# monitoring_1.net
KiCad netlist of a schematic drawn in EAGLE
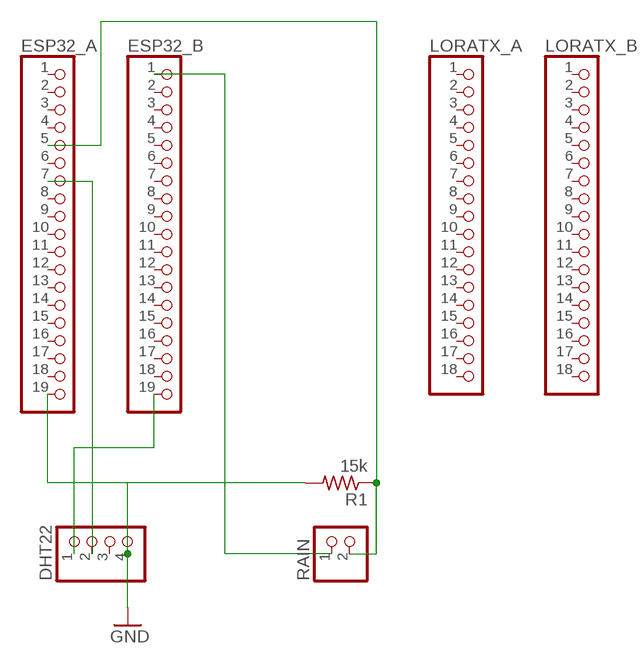
[diagram p0: schematic, sheet 1]

(export (version "E")
  (design (tool "Eeschema 10.0.6"))
  (components
    (comp (ref "DHT22")
      (value "PINHD-1X4")
      (footprint "eagle-import:1X04")
      (libsource (lib "eagle-import") (part "PINHD-1X4"))
    )
    (comp (ref "ESP32_A")
      (value "PINHD-1X19")
      (footprint "eagle-import:1X19")
      (libsource (lib "eagle-import") (part "PINHD-1X19"))
    )
    (comp (ref "ESP32_B")
      (value "PINHD-1X19")
      (footprint "eagle-import:1X19")
      (libsource (lib "eagle-import") (part "PINHD-1X19"))
    )
    (comp (ref "LORATX_A")
      (value "PINHD-1X18")
      (footprint "eagle-import:1X18")
      (libsource (lib "eagle-import") (part "PINHD-1X18"))
    )
    (comp (ref "LORATX_B")
      (value "PINHD-1X18")
      (footprint "eagle-import:1X18")
      (libsource (lib "eagle-import") (part "PINHD-1X18"))
    )
    (comp (ref "R1")
      (value "15k")
      (footprint "eagle-import:0204_7")
      (libsource (lib "eagle-import") (part "R-US_0204/7"))
    )
    (comp (ref "RAIN")
      (value "PINHD-1X2")
      (footprint "eagle-import:1X02")
      (libsource (lib "eagle-import") (part "PINHD-1X2"))
    )
  )
  (nets
    (net (code "1") (name "GND") (class "Default")
      (node (ref "DHT22") (pin "4") (pinfunction "4_4") (pintype "passive"))
      (node (ref "ESP32_A") (pin "19") (pinfunction "19_19") (pintype "passive"))
      (node (ref "R1") (pin "2") (pinfunction "2_2") (pintype "passive"))
    )
    (net (code "2") (name "Net-(DHT22-Pad1)") (class "Default")
      (node (ref "DHT22") (pin "1") (pinfunction "1_1") (pintype "passive"))
      (node (ref "ESP32_B") (pin "19") (pinfunction "19_19") (pintype "passive"))
    )
    (net (code "3") (name "Net-(DHT22-Pad2)") (class "Default")
      (node (ref "DHT22") (pin "2") (pinfunction "2_2") (pintype "passive"))
      (node (ref "ESP32_A") (pin "7") (pinfunction "7_7") (pintype "passive"))
    )
    (net (code "4") (name "Net-(ESP32_A-Pad5)") (class "Default")
      (node (ref "ESP32_A") (pin "5") (pinfunction "5_5") (pintype "passive"))
      (node (ref "R1") (pin "1") (pinfunction "1_1") (pintype "passive"))
      (node (ref "RAIN") (pin "2") (pinfunction "2_2") (pintype "passive"))
    )
    (net (code "5") (name "Net-(ESP32_B-Pad1)") (class "Default")
      (node (ref "ESP32_B") (pin "1") (pinfunction "1_1") (pintype "passive"))
      (node (ref "RAIN") (pin "1") (pinfunction "1_1") (pintype "passive"))
    )
    (net (code "6") (name "unconnected-(DHT22-Pad3)") (class "Default")
      (node (ref "DHT22") (pin "3") (pinfunction "3_3") (pintype "passive"))
    )
    (net (code "7") (name "unconnected-(ESP32_A-Pad1)") (class "Default")
      (node (ref "ESP32_A") (pin "1") (pinfunction "1_1") (pintype "passive"))
    )
    (net (code "8") (name "unconnected-(ESP32_A-Pad2)") (class "Default")
      (node (ref "ESP32_A") (pin "2") (pinfunction "2_2") (pintype "passive"))
    )
    (net (code "9") (name "unconnected-(ESP32_A-Pad3)") (class "Default")
      (node (ref "ESP32_A") (pin "3") (pinfunction "3_3") (pintype "passive"))
    )
    (net (code "10") (name "unconnected-(ESP32_A-Pad4)") (class "Default")
      (node (ref "ESP32_A") (pin "4") (pinfunction "4_4") (pintype "passive"))
    )
    (net (code "11") (name "unconnected-(ESP32_A-Pad6)") (class "Default")
      (node (ref "ESP32_A") (pin "6") (pinfunction "6_6") (pintype "passive"))
    )
    (net (code "12") (name "unconnected-(ESP32_A-Pad8)") (class "Default")
      (node (ref "ESP32_A") (pin "8") (pinfunction "8_8") (pintype "passive"))
    )
    (net (code "13") (name "unconnected-(ESP32_A-Pad9)") (class "Default")
      (node (ref "ESP32_A") (pin "9") (pinfunction "9_9") (pintype "passive"))
    )
    (net (code "14") (name "unconnected-(ESP32_A-Pad10)") (class "Default")
      (node (ref "ESP32_A") (pin "10") (pinfunction "10_10") (pintype "passive"))
    )
    (net (code "15") (name "unconnected-(ESP32_A-Pad11)") (class "Default")
      (node (ref "ESP32_A") (pin "11") (pinfunction "11_11") (pintype "passive"))
    )
    (net (code "16") (name "unconnected-(ESP32_A-Pad12)") (class "Default")
      (node (ref "ESP32_A") (pin "12") (pinfunction "12_12") (pintype "passive"))
    )
    (net (code "17") (name "unconnected-(ESP32_A-Pad13)") (class "Default")
      (node (ref "ESP32_A") (pin "13") (pinfunction "13_13") (pintype "passive"))
    )
    (net (code "18") (name "unconnected-(ESP32_A-Pad14)") (class "Default")
      (node (ref "ESP32_A") (pin "14") (pinfunction "14_14") (pintype "passive"))
    )
    (net (code "19") (name "unconnected-(ESP32_A-Pad15)") (class "Default")
      (node (ref "ESP32_A") (pin "15") (pinfunction "15_15") (pintype "passive"))
    )
    (net (code "20") (name "unconnected-(ESP32_A-Pad16)") (class "Default")
      (node (ref "ESP32_A") (pin "16") (pinfunction "16_16") (pintype "passive"))
    )
    (net (code "21") (name "unconnected-(ESP32_A-Pad17)") (class "Default")
      (node (ref "ESP32_A") (pin "17") (pinfunction "17_17") (pintype "passive"))
    )
    (net (code "22") (name "unconnected-(ESP32_A-Pad18)") (class "Default")
      (node (ref "ESP32_A") (pin "18") (pinfunction "18_18") (pintype "passive"))
    )
    (net (code "23") (name "unconnected-(ESP32_B-Pad2)") (class "Default")
      (node (ref "ESP32_B") (pin "2") (pinfunction "2_2") (pintype "passive"))
    )
    (net (code "24") (name "unconnected-(ESP32_B-Pad3)") (class "Default")
      (node (ref "ESP32_B") (pin "3") (pinfunction "3_3") (pintype "passive"))
    )
    (net (code "25") (name "unconnected-(ESP32_B-Pad4)") (class "Default")
      (node (ref "ESP32_B") (pin "4") (pinfunction "4_4") (pintype "passive"))
    )
    (net (code "26") (name "unconnected-(ESP32_B-Pad5)") (class "Default")
      (node (ref "ESP32_B") (pin "5") (pinfunction "5_5") (pintype "passive"))
    )
    (net (code "27") (name "unconnected-(ESP32_B-Pad6)") (class "Default")
      (node (ref "ESP32_B") (pin "6") (pinfunction "6_6") (pintype "passive"))
    )
    (net (code "28") (name "unconnected-(ESP32_B-Pad7)") (class "Default")
      (node (ref "ESP32_B") (pin "7") (pinfunction "7_7") (pintype "passive"))
    )
    (net (code "29") (name "unconnected-(ESP32_B-Pad8)") (class "Default")
      (node (ref "ESP32_B") (pin "8") (pinfunction "8_8") (pintype "passive"))
    )
    (net (code "30") (name "unconnected-(ESP32_B-Pad9)") (class "Default")
      (node (ref "ESP32_B") (pin "9") (pinfunction "9_9") (pintype "passive"))
    )
    (net (code "31") (name "unconnected-(ESP32_B-Pad10)") (class "Default")
      (node (ref "ESP32_B") (pin "10") (pinfunction "10_10") (pintype "passive"))
    )
    (net (code "32") (name "unconnected-(ESP32_B-Pad11)") (class "Default")
      (node (ref "ESP32_B") (pin "11") (pinfunction "11_11") (pintype "passive"))
    )
    (net (code "33") (name "unconnected-(ESP32_B-Pad12)") (class "Default")
      (node (ref "ESP32_B") (pin "12") (pinfunction "12_12") (pintype "passive"))
    )
    (net (code "34") (name "unconnected-(ESP32_B-Pad13)") (class "Default")
      (node (ref "ESP32_B") (pin "13") (pinfunction "13_13") (pintype "passive"))
    )
    (net (code "35") (name "unconnected-(ESP32_B-Pad14)") (class "Default")
      (node (ref "ESP32_B") (pin "14") (pinfunction "14_14") (pintype "passive"))
    )
    (net (code "36") (name "unconnected-(ESP32_B-Pad15)") (class "Default")
      (node (ref "ESP32_B") (pin "15") (pinfunction "15_15") (pintype "passive"))
    )
    (net (code "37") (name "unconnected-(ESP32_B-Pad16)") (class "Default")
      (node (ref "ESP32_B") (pin "16") (pinfunction "16_16") (pintype "passive"))
    )
    (net (code "38") (name "unconnected-(ESP32_B-Pad17)") (class "Default")
      (node (ref "ESP32_B") (pin "17") (pinfunction "17_17") (pintype "passive"))
    )
    (net (code "39") (name "unconnected-(ESP32_B-Pad18)") (class "Default")
      (node (ref "ESP32_B") (pin "18") (pinfunction "18_18") (pintype "passive"))
    )
    (net (code "40") (name "unconnected-(LORATX_A-Pad1)") (class "Default")
      (node (ref "LORATX_A") (pin "1") (pinfunction "1_1") (pintype "passive"))
    )
    (net (code "41") (name "unconnected-(LORATX_A-Pad2)") (class "Default")
      (node (ref "LORATX_A") (pin "2") (pinfunction "2_2") (pintype "passive"))
    )
    (net (code "42") (name "unconnected-(LORATX_A-Pad3)") (class "Default")
      (node (ref "LORATX_A") (pin "3") (pinfunction "3_3") (pintype "passive"))
    )
    (net (code "43") (name "unconnected-(LORATX_A-Pad4)") (class "Default")
      (node (ref "LORATX_A") (pin "4") (pinfunction "4_4") (pintype "passive"))
    )
    (net (code "44") (name "unconnected-(LORATX_A-Pad5)") (class "Default")
      (node (ref "LORATX_A") (pin "5") (pinfunction "5_5") (pintype "passive"))
    )
    (net (code "45") (name "unconnected-(LORATX_A-Pad6)") (class "Default")
      (node (ref "LORATX_A") (pin "6") (pinfunction "6_6") (pintype "passive"))
    )
    (net (code "46") (name "unconnected-(LORATX_A-Pad7)") (class "Default")
      (node (ref "LORATX_A") (pin "7") (pinfunction "7_7") (pintype "passive"))
    )
    (net (code "47") (name "unconnected-(LORATX_A-Pad8)") (class "Default")
      (node (ref "LORATX_A") (pin "8") (pinfunction "8_8") (pintype "passive"))
    )
    (net (code "48") (name "unconnected-(LORATX_A-Pad9)") (class "Default")
      (node (ref "LORATX_A") (pin "9") (pinfunction "9_9") (pintype "passive"))
    )
    (net (code "49") (name "unconnected-(LORATX_A-Pad10)") (class "Default")
      (node (ref "LORATX_A") (pin "10") (pinfunction "10_10") (pintype "passive"))
    )
    (net (code "50") (name "unconnected-(LORATX_A-Pad11)") (class "Default")
      (node (ref "LORATX_A") (pin "11") (pinfunction "11_11") (pintype "passive"))
    )
    (net (code "51") (name "unconnected-(LORATX_A-Pad12)") (class "Default")
      (node (ref "LORATX_A") (pin "12") (pinfunction "12_12") (pintype "passive"))
    )
    (net (code "52") (name "unconnected-(LORATX_A-Pad13)") (class "Default")
      (node (ref "LORATX_A") (pin "13") (pinfunction "13_13") (pintype "passive"))
    )
    (net (code "53") (name "unconnected-(LORATX_A-Pad14)") (class "Default")
      (node (ref "LORATX_A") (pin "14") (pinfunction "14_14") (pintype "passive"))
    )
    (net (code "54") (name "unconnected-(LORATX_A-Pad15)") (class "Default")
      (node (ref "LORATX_A") (pin "15") (pinfunction "15_15") (pintype "passive"))
    )
    (net (code "55") (name "unconnected-(LORATX_A-Pad16)") (class "Default")
      (node (ref "LORATX_A") (pin "16") (pinfunction "16_16") (pintype "passive"))
    )
    (net (code "56") (name "unconnected-(LORATX_A-Pad17)") (class "Default")
      (node (ref "LORATX_A") (pin "17") (pinfunction "17_17") (pintype "passive"))
    )
    (net (code "57") (name "unconnected-(LORATX_A-Pad18)") (class "Default")
      (node (ref "LORATX_A") (pin "18") (pinfunction "18_18") (pintype "passive"))
    )
    (net (code "58") (name "unconnected-(LORATX_B-Pad1)") (class "Default")
      (node (ref "LORATX_B") (pin "1") (pinfunction "1_1") (pintype "passive"))
    )
    (net (code "59") (name "unconnected-(LORATX_B-Pad2)") (class "Default")
      (node (ref "LORATX_B") (pin "2") (pinfunction "2_2") (pintype "passive"))
    )
    (net (code "60") (name "unconnected-(LORATX_B-Pad3)") (class "Default")
      (node (ref "LORATX_B") (pin "3") (pinfunction "3_3") (pintype "passive"))
    )
    (net (code "61") (name "unconnected-(LORATX_B-Pad4)") (class "Default")
      (node (ref "LORATX_B") (pin "4") (pinfunction "4_4") (pintype "passive"))
    )
    (net (code "62") (name "unconnected-(LORATX_B-Pad5)") (class "Default")
      (node (ref "LORATX_B") (pin "5") (pinfunction "5_5") (pintype "passive"))
    )
    (net (code "63") (name "unconnected-(LORATX_B-Pad6)") (class "Default")
      (node (ref "LORATX_B") (pin "6") (pinfunction "6_6") (pintype "passive"))
    )
    (net (code "64") (name "unconnected-(LORATX_B-Pad7)") (class "Default")
      (node (ref "LORATX_B") (pin "7") (pinfunction "7_7") (pintype "passive"))
    )
    (net (code "65") (name "unconnected-(LORATX_B-Pad8)") (class "Default")
      (node (ref "LORATX_B") (pin "8") (pinfunction "8_8") (pintype "passive"))
    )
    (net (code "66") (name "unconnected-(LORATX_B-Pad9)") (class "Default")
      (node (ref "LORATX_B") (pin "9") (pinfunction "9_9") (pintype "passive"))
    )
    (net (code "67") (name "unconnected-(LORATX_B-Pad10)") (class "Default")
      (node (ref "LORATX_B") (pin "10") (pinfunction "10_10") (pintype "passive"))
    )
    (net (code "68") (name "unconnected-(LORATX_B-Pad11)") (class "Default")
      (node (ref "LORATX_B") (pin "11") (pinfunction "11_11") (pintype "passive"))
    )
    (net (code "69") (name "unconnected-(LORATX_B-Pad12)") (class "Default")
      (node (ref "LORATX_B") (pin "12") (pinfunction "12_12") (pintype "passive"))
    )
    (net (code "70") (name "unconnected-(LORATX_B-Pad13)") (class "Default")
      (node (ref "LORATX_B") (pin "13") (pinfunction "13_13") (pintype "passive"))
    )
    (net (code "71") (name "unconnected-(LORATX_B-Pad14)") (class "Default")
      (node (ref "LORATX_B") (pin "14") (pinfunction "14_14") (pintype "passive"))
    )
    (net (code "72") (name "unconnected-(LORATX_B-Pad15)") (class "Default")
      (node (ref "LORATX_B") (pin "15") (pinfunction "15_15") (pintype "passive"))
    )
    (net (code "73") (name "unconnected-(LORATX_B-Pad16)") (class "Default")
      (node (ref "LORATX_B") (pin "16") (pinfunction "16_16") (pintype "passive"))
    )
    (net (code "74") (name "unconnected-(LORATX_B-Pad17)") (class "Default")
      (node (ref "LORATX_B") (pin "17") (pinfunction "17_17") (pintype "passive"))
    )
    (net (code "75") (name "unconnected-(LORATX_B-Pad18)") (class "Default")
      (node (ref "LORATX_B") (pin "18") (pinfunction "18_18") (pintype "passive"))
    )
  )
)
